# power.net
KiCad netlist of a schematic drawn in Altium Designer
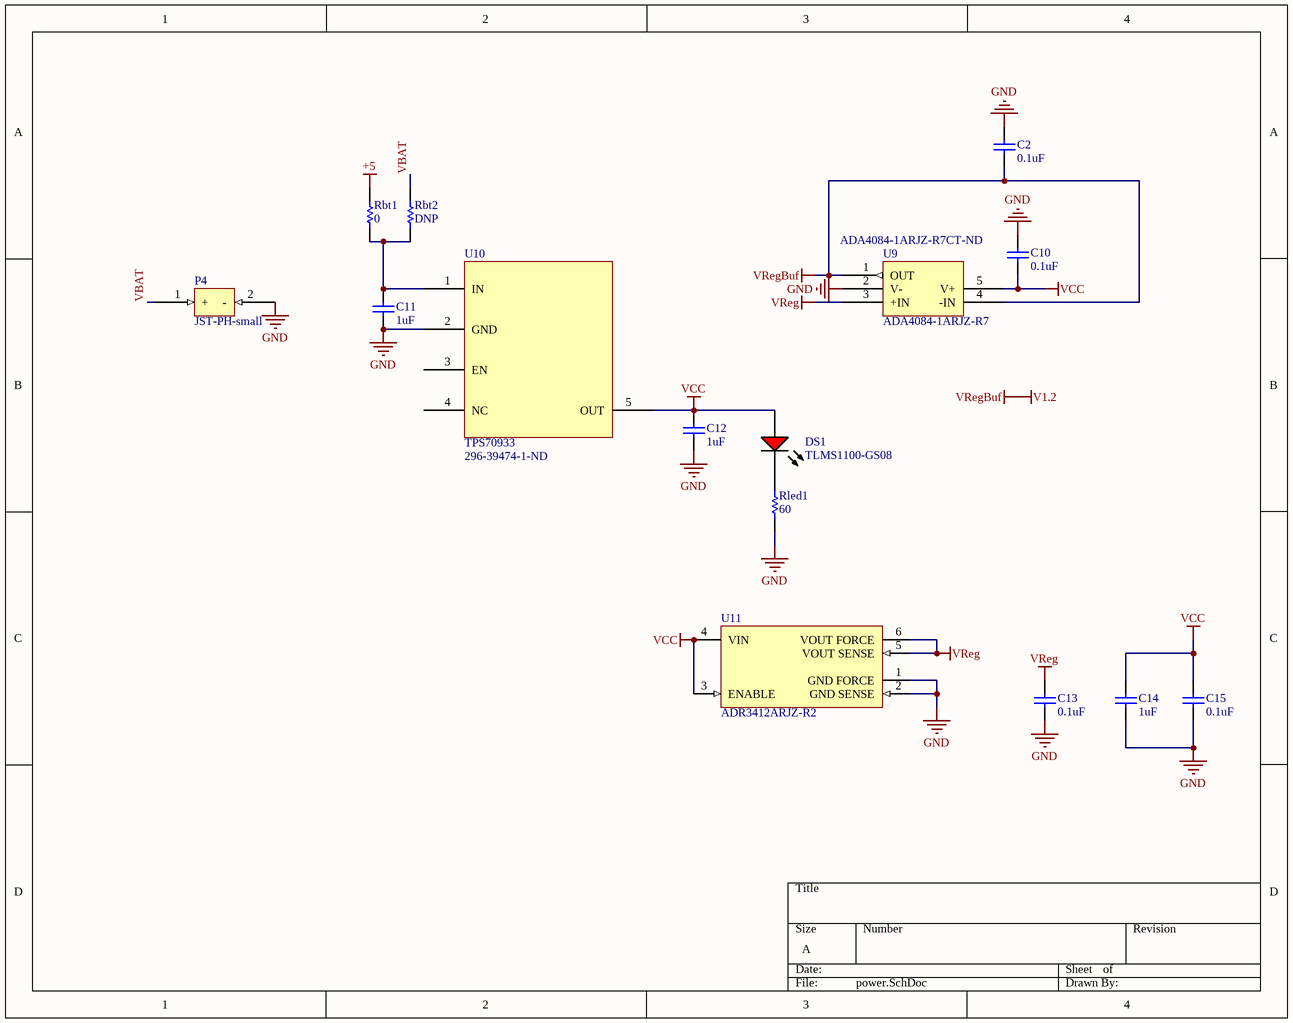
[diagram p0: power.SchDoc]

(export (version "E")
  (design (tool "Eeschema 10.0.6"))
  (components
    (comp (ref "C2")
      (value "0.1uF")
      (footprint "0402")
      (description "Ceramic Capacitor (Surface Mount)")
      (fields (field (name "MANUFACTURER") "Generic Ceramic Chip Cap (TBD)") (field (name "Comment") "Cap"))
      (libsource (lib "maglib") (part "Cap"))
    )
    (comp (ref "C10")
      (value "0.1uF")
      (footprint "0402")
      (description "Ceramic Capacitor (Surface Mount)")
      (fields (field (name "MANUFACTURER") "Generic Ceramic Chip Cap (TBD)") (field (name "Comment") "Cap"))
      (libsource (lib "maglib") (part "Cap"))
    )
    (comp (ref "C11")
      (value "1uF")
      (footprint "0402")
      (description "Ceramic Capacitor (Surface Mount)")
      (fields (field (name "MANUFACTURER") "Generic Ceramic Chip Cap (TBD)") (field (name "Comment") "Cap"))
      (libsource (lib "maglib") (part "Cap"))
    )
    (comp (ref "C12")
      (value "1uF")
      (footprint "0402")
      (description "Ceramic Capacitor (Surface Mount)")
      (fields (field (name "MANUFACTURER") "Generic Ceramic Chip Cap (TBD)") (field (name "Comment") "Cap"))
      (libsource (lib "maglib") (part "Cap"))
    )
    (comp (ref "C13")
      (value "0.1uF")
      (footprint "0402")
      (description "Ceramic Capacitor (Surface Mount)")
      (fields (field (name "MANUFACTURER") "Generic Ceramic Chip Cap (TBD)") (field (name "Comment") "Cap"))
      (libsource (lib "maglib") (part "Cap"))
    )
    (comp (ref "C14")
      (value "1uF")
      (footprint "0402")
      (description "Ceramic Capacitor (Surface Mount)")
      (fields (field (name "MANUFACTURER") "Generic Ceramic Chip Cap (TBD)") (field (name "Comment") "Cap"))
      (libsource (lib "maglib") (part "Cap"))
    )
    (comp (ref "C15")
      (value "0.1uF")
      (footprint "0402")
      (description "Ceramic Capacitor (Surface Mount)")
      (fields (field (name "MANUFACTURER") "Generic Ceramic Chip Cap (TBD)") (field (name "Comment") "Cap"))
      (libsource (lib "maglib") (part "Cap"))
    )
    (comp (ref "DS1")
      (value "TLMS1100-GS08")
      (footprint "VISH-TLMX1100_V")
      (description "LED, RED, 2.1 V, -40 to 100 degC, 2-Pin SMD (0603), RoHS, Tape and Reel")
      (fields (field (name "TOLERANCE") "5%"))
      (libsource (lib "Altium Content Vault") (part "LED-RED-AK-2"))
    )
    (comp (ref "P4")
      (value "JST-PH-small")
      (footprint "JST-PH-small")
      (libsource (lib "maglib") (part "JST-PH-small"))
    )
    (comp (ref "Rbt1")
      (value "0")
      (footprint "0402")
      (description "Chip Resistor (Surface Mount)")
      (fields (field (name "MANUFACTURER") "Generic Chip Res (TBD)") (field (name "Comment") "Res"))
      (libsource (lib "maglib") (part "Res"))
    )
    (comp (ref "Rbt2")
      (value "DNP")
      (footprint "0402")
      (description "Chip Resistor (Surface Mount)")
      (fields (field (name "MANUFACTURER") "Generic Chip Res (TBD)") (field (name "Comment") "Res"))
      (libsource (lib "maglib") (part "Res"))
    )
    (comp (ref "Rled1")
      (value "60")
      (footprint "0402")
      (description "Chip Resistor (Surface Mount)")
      (fields (field (name "MANUFACTURER") "Generic Chip Res (TBD)") (field (name "Comment") "Res"))
      (libsource (lib "maglib") (part "Res"))
    )
    (comp (ref "U9")
      (value "ADA4084-1ARJZ-R7")
      (footprint "SOT95P280X145-5N")
      (description "30 V, 8 MHz, Low Bias Current,\r\nSingle-Supply, RRO, Precision Op Amps")
      (fields (field (name "SUPPLIER PART NUMBER 1") "ADA4084-1ARJZ-R7CT-ND"))
      (libsource (lib "maglib") (part "ADA4622-1ARJZ"))
    )
    (comp (ref "U10")
      (value "TPS70933")
      (footprint "SOT95P280X145-5N")
      (description "3.3V Ultra low power Voltage Regulator")
      (fields (field (name "SUPPLIER PART NUMBER 1") "296-39474-1-ND"))
      (libsource (lib "maglib") (part "TPS70933"))
    )
    (comp (ref "U11")
      (value "ADR3412ARJZ-R2")
      (footprint "ADI-RJ-6_N")
      (fields (field (name "MANUFACTURER") "Analog Devices"))
      (libsource (lib "Altium Content Vault") (part "ADI-ADR34xx-RJ-6"))
    )
  )
  (nets
    (net (code "1") (name "+5") (class "Default")
      (node (ref "Rbt1") (pin "2") (pinfunction "2_2") (pintype "passive"))
    )
    (net (code "2") (name "/VBAT") (class "Default")
      (node (ref "P4") (pin "1") (pinfunction "+_1") (pintype "input"))
      (node (ref "Rbt2") (pin "2") (pinfunction "2_2") (pintype "passive"))
    )
    (net (code "3") (name "GND") (class "Default")
      (node (ref "C10") (pin "2") (pinfunction "2_2") (pintype "passive"))
      (node (ref "C11") (pin "2") (pinfunction "2_2") (pintype "passive"))
      (node (ref "C12") (pin "2") (pinfunction "2_2") (pintype "passive"))
      (node (ref "C13") (pin "1") (pinfunction "1_1") (pintype "passive"))
      (node (ref "C14") (pin "2") (pinfunction "2_2") (pintype "passive"))
      (node (ref "C15") (pin "1") (pinfunction "1_1") (pintype "passive"))
      (node (ref "C2") (pin "2") (pinfunction "2_2") (pintype "passive"))
      (node (ref "P4") (pin "2") (pinfunction "-_2") (pintype "input"))
      (node (ref "Rled1") (pin "1") (pinfunction "1_1") (pintype "passive"))
      (node (ref "U10") (pin "2") (pinfunction "GND_2") (pintype "passive"))
      (node (ref "U11") (pin "1") (pinfunction "GND_FORCE_1") (pintype "power_in"))
      (node (ref "U11") (pin "2") (pinfunction "GND_SENSE_2") (pintype "input"))
      (node (ref "U9") (pin "2") (pinfunction "V-_2") (pintype "power_in"))
    )
    (net (code "4") (name "Net-(DS1-K)") (class "Default")
      (node (ref "DS1") (pin "2") (pinfunction "K_2") (pintype "passive"))
      (node (ref "Rled1") (pin "2") (pinfunction "2_2") (pintype "passive"))
    )
    (net (code "5") (name "Net-(U10-IN)") (class "Default")
      (node (ref "C11") (pin "1") (pinfunction "1_1") (pintype "passive"))
      (node (ref "Rbt1") (pin "1") (pinfunction "1_1") (pintype "passive"))
      (node (ref "Rbt2") (pin "1") (pinfunction "1_1") (pintype "passive"))
      (node (ref "U10") (pin "1") (pinfunction "IN_1") (pintype "passive"))
    )
    (net (code "6") (name "V1.2") (class "Default")
      (node (ref "C2") (pin "1") (pinfunction "1_1") (pintype "passive"))
      (node (ref "U9") (pin "1") (pinfunction "OUT_1") (pintype "output"))
      (node (ref "U9") (pin "4") (pinfunction "-IN_4") (pintype "passive"))
    )
    (net (code "7") (name "VCC") (class "Default")
      (node (ref "C10") (pin "1") (pinfunction "1_1") (pintype "passive"))
      (node (ref "C12") (pin "1") (pinfunction "1_1") (pintype "passive"))
      (node (ref "C14") (pin "1") (pinfunction "1_1") (pintype "passive"))
      (node (ref "C15") (pin "2") (pinfunction "2_2") (pintype "passive"))
      (node (ref "DS1") (pin "1") (pinfunction "A_1") (pintype "passive"))
      (node (ref "U10") (pin "5") (pinfunction "OUT_5") (pintype "passive"))
      (node (ref "U11") (pin "3") (pinfunction "ENABLE_3") (pintype "input"))
      (node (ref "U11") (pin "4") (pinfunction "VIN_4") (pintype "power_in"))
      (node (ref "U9") (pin "5") (pinfunction "V+_5") (pintype "power_in"))
    )
    (net (code "8") (name "VReg") (class "Default")
      (node (ref "C13") (pin "2") (pinfunction "2_2") (pintype "passive"))
      (node (ref "U11") (pin "5") (pinfunction "VOUT_SENSE_5") (pintype "input"))
      (node (ref "U11") (pin "6") (pinfunction "VOUT_FORCE_6") (pintype "power_in"))
      (node (ref "U9") (pin "3") (pinfunction "+IN_3") (pintype "passive"))
    )
    (net (code "9") (name "unconnected-(U10-EN-Pad3)") (class "Default")
      (node (ref "U10") (pin "3") (pinfunction "EN_3") (pintype "passive"))
    )
    (net (code "10") (name "unconnected-(U10-NC-Pad4)") (class "Default")
      (node (ref "U10") (pin "4") (pinfunction "NC_4") (pintype "passive"))
    )
  )
)
